# OSSI-1_LED_Controller.net
KiCad netlist of a schematic drawn in EAGLE
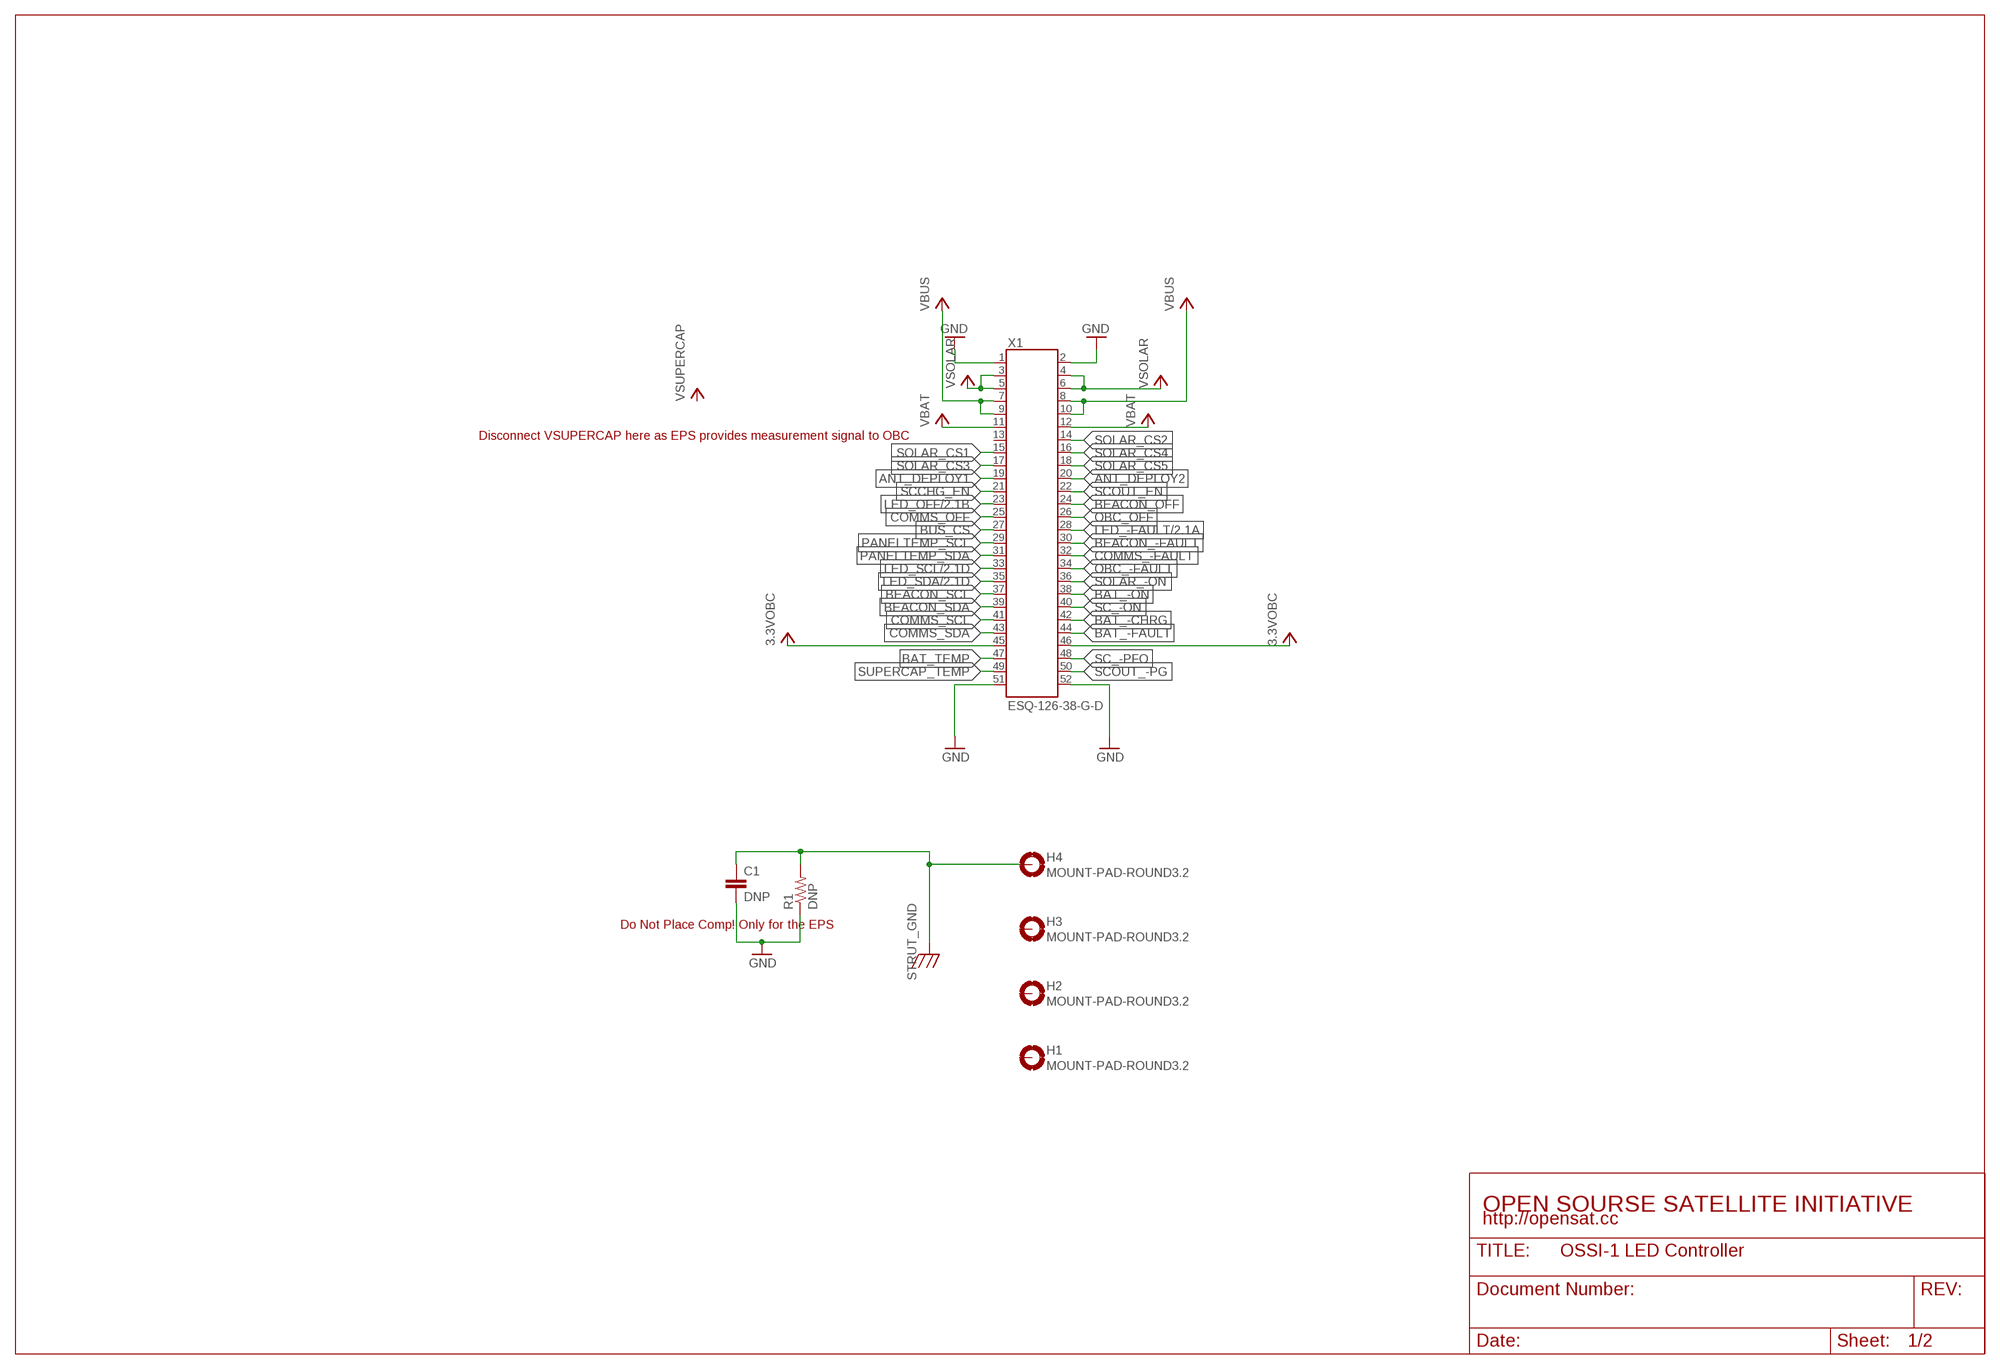
[diagram p0: schematic, sheet 1]
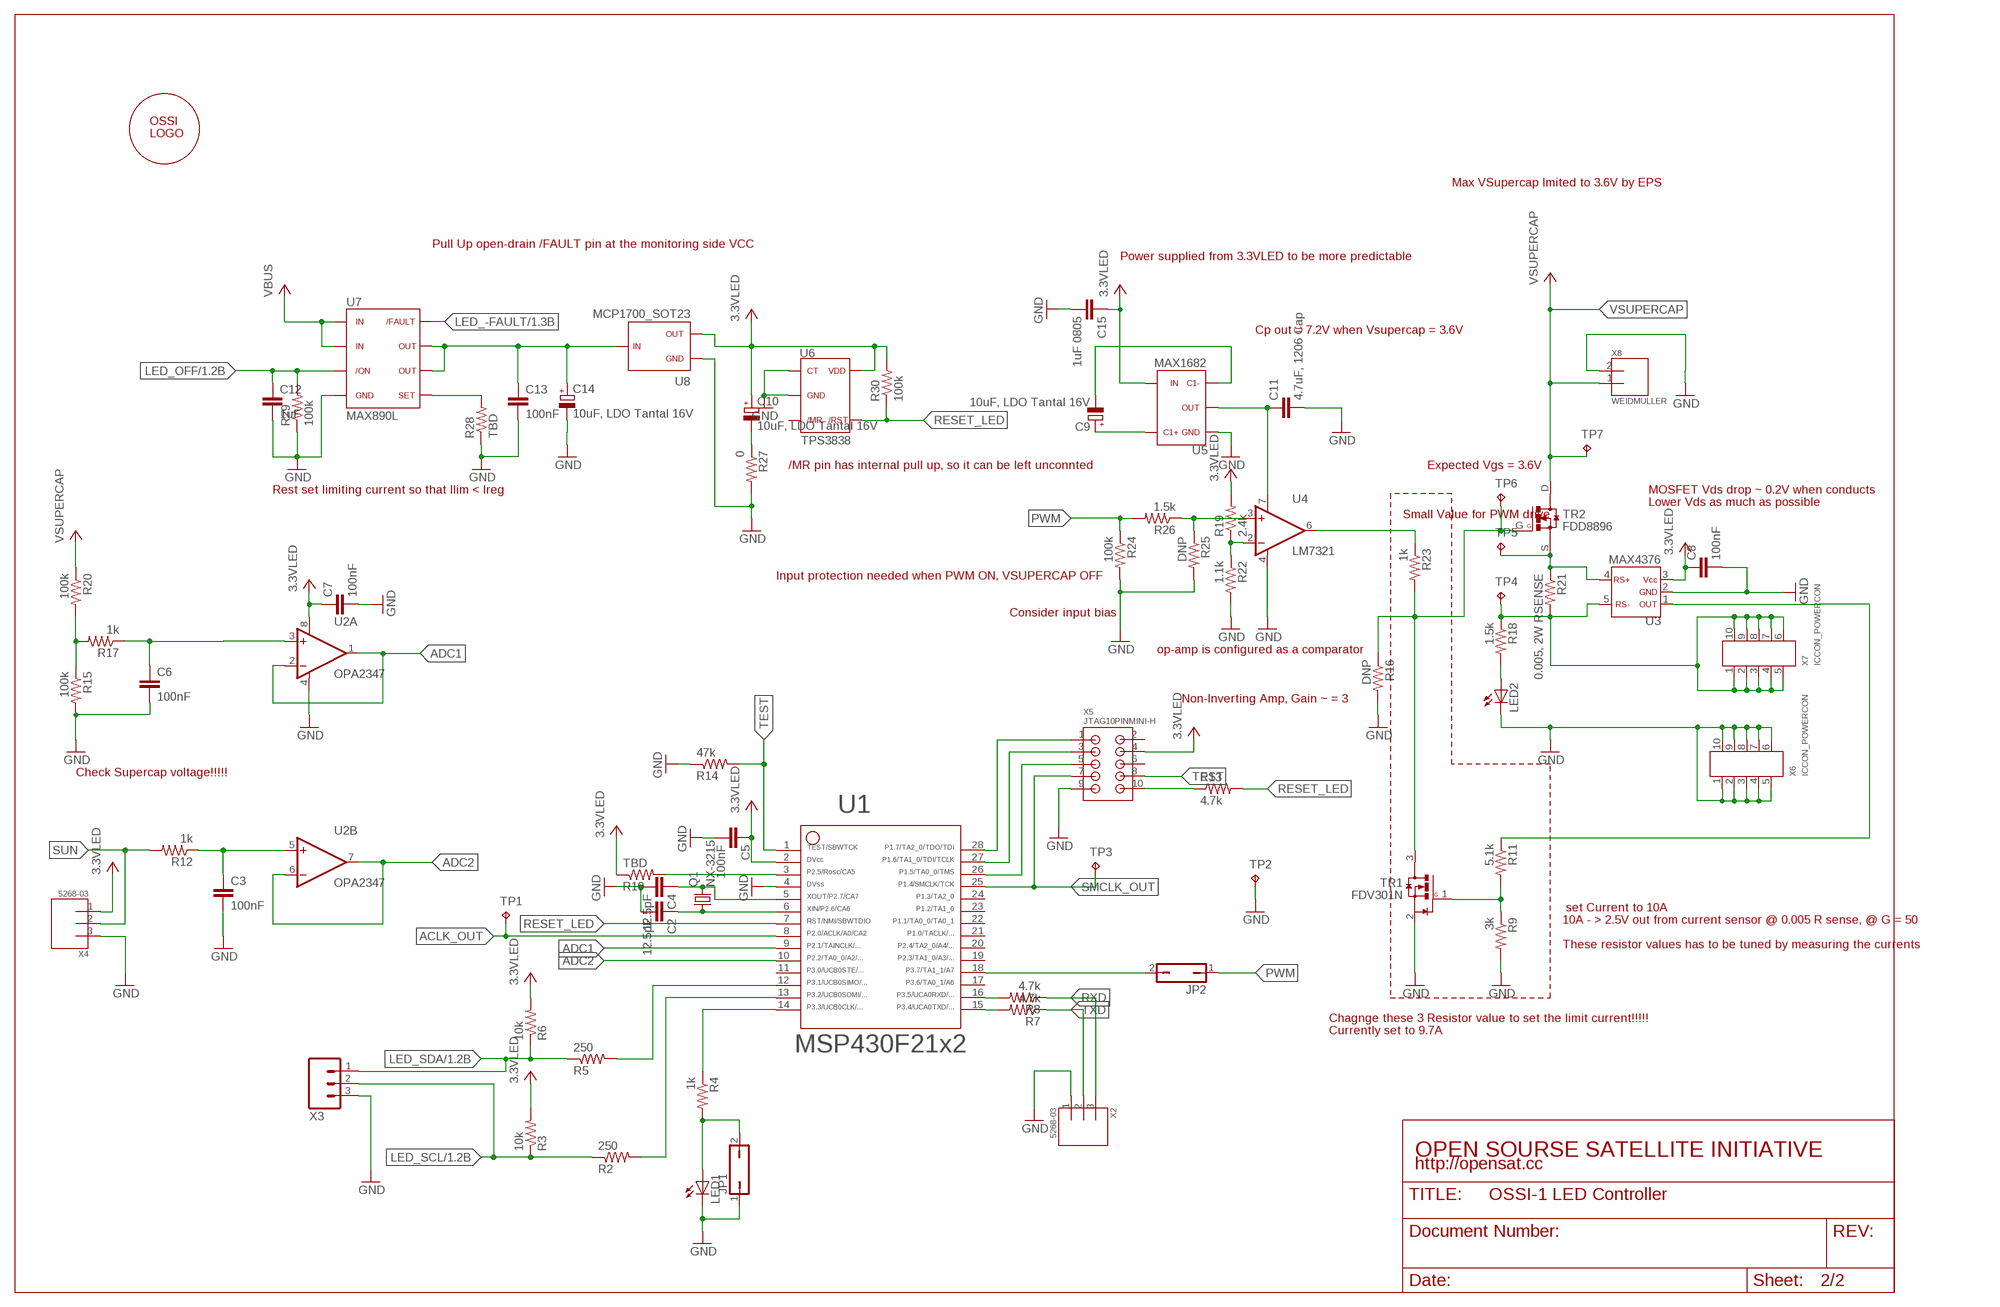
[diagram p1: schematic, sheet 2]

(export (version "E")
  (design (tool "Eeschema 10.0.6"))
  (components
    (comp (ref "C1")
      (value "DNP")
      (footprint "eagle-import:C0805(2012)")
      (libsource (lib "eagle-import") (part "C0805(2012)"))
    )
    (comp (ref "H1")
      (value "MOUNT-PAD-ROUND3.2")
      (footprint "eagle-import:3.2-PAD-ROUND")
      (libsource (lib "eagle-import") (part "MOUNT-PAD-ROUND3.2"))
    )
    (comp (ref "H2")
      (value "MOUNT-PAD-ROUND3.2")
      (footprint "eagle-import:3.2-PAD-ROUND")
      (libsource (lib "eagle-import") (part "MOUNT-PAD-ROUND3.2"))
    )
    (comp (ref "H3")
      (value "MOUNT-PAD-ROUND3.2")
      (footprint "eagle-import:3.2-PAD-ROUND")
      (libsource (lib "eagle-import") (part "MOUNT-PAD-ROUND3.2"))
    )
    (comp (ref "H4")
      (value "MOUNT-PAD-ROUND3.2")
      (footprint "eagle-import:3.2-PAD-ROUND")
      (libsource (lib "eagle-import") (part "MOUNT-PAD-ROUND3.2"))
    )
    (comp (ref "R1")
      (value "DNP")
      (footprint "eagle-import:WSL1206")
      (libsource (lib "eagle-import") (part "RWSL1206"))
    )
    (comp (ref "X1")
      (value "ESQ-126-38-G-D")
      (footprint "eagle-import:ESQ-126-XX-X-D")
      (libsource (lib "eagle-import") (part "ESQ-126-38-G-D"))
    )
    (comp (ref "C2")
      (value "12.5pF")
      (footprint "eagle-import:C0603(1608)")
      (libsource (lib "eagle-import") (part "C0603(1608)"))
    )
    (comp (ref "C3")
      (value "100nF")
      (footprint "eagle-import:C0603(1608)")
      (libsource (lib "eagle-import") (part "C0603(1608)"))
    )
    (comp (ref "C4")
      (value "12.5pF")
      (footprint "eagle-import:C0603(1608)")
      (libsource (lib "eagle-import") (part "C0603(1608)"))
    )
    (comp (ref "C5")
      (value "100nF")
      (footprint "eagle-import:C0603(1608)")
      (libsource (lib "eagle-import") (part "C0603(1608)"))
    )
    (comp (ref "C6")
      (value "100nF")
      (footprint "eagle-import:C0603(1608)")
      (libsource (lib "eagle-import") (part "C0603(1608)"))
    )
    (comp (ref "C7")
      (value "100nF")
      (footprint "eagle-import:C0603(1608)")
      (libsource (lib "eagle-import") (part "C0603(1608)"))
    )
    (comp (ref "C8")
      (value "100nF")
      (footprint "eagle-import:C0603(1608)")
      (libsource (lib "eagle-import") (part "C0603(1608)"))
    )
    (comp (ref "C9")
      (value "10uF, LDO Tantal 16V")
      (footprint "eagle-import:C1206(3216)-A")
      (libsource (lib "eagle-import") (part "C-TANTAL-A"))
    )
    (comp (ref "C10")
      (value "10uF, LDO Tantal 16V")
      (footprint "eagle-import:C1206(3216)-A")
      (libsource (lib "eagle-import") (part "C-TANTAL-A"))
    )
    (comp (ref "C11")
      (value "4.7uF, 1206 Cap")
      (footprint "eagle-import:C1206-GCM31")
      (libsource (lib "eagle-import") (part "C1206(3216)-GCM31"))
    )
    (comp (ref "C12")
      (value "1uF")
      (footprint "eagle-import:C0603(1608)")
      (libsource (lib "eagle-import") (part "C0603(1608)"))
    )
    (comp (ref "C13")
      (value "100nF")
      (footprint "eagle-import:C0603(1608)")
      (libsource (lib "eagle-import") (part "C0603(1608)"))
    )
    (comp (ref "C14")
      (value "10uF, LDO Tantal 16V")
      (footprint "eagle-import:C1206(3216)-A")
      (libsource (lib "eagle-import") (part "C-TANTAL-A"))
    )
    (comp (ref "C15")
      (value "1uF 0805")
      (footprint "eagle-import:C0805(2012)")
      (libsource (lib "eagle-import") (part "C0805(2012)"))
    )
    (comp (ref "JP1")
      (value "JP1Q")
      (footprint "eagle-import:JP1")
      (libsource (lib "eagle-import") (part "JP1Q"))
    )
    (comp (ref "JP2")
      (value "JP1Q")
      (footprint "eagle-import:JP1")
      (libsource (lib "eagle-import") (part "JP1Q"))
    )
    (comp (ref "LED1")
      (value "LED0603")
      (footprint "eagle-import:LED-0603")
      (libsource (lib "eagle-import") (part "LED0603"))
    )
    (comp (ref "LED2")
      (value "LEDCHIPLED_0603")
      (footprint "eagle-import:CHIPLED_0603")
      (libsource (lib "eagle-import") (part "LEDCHIPLED_0603"))
    )
    (comp (ref "Q1")
      (value "NX-3215")
      (footprint "eagle-import:NX-3215")
      (libsource (lib "eagle-import") (part "NX-3215"))
    )
    (comp (ref "R2")
      (value "250")
      (footprint "eagle-import:R0603(1608)")
      (libsource (lib "eagle-import") (part "R0603(1608)"))
    )
    (comp (ref "R3")
      (value "10k")
      (footprint "eagle-import:R0603(1608)")
      (libsource (lib "eagle-import") (part "R0603(1608)"))
    )
    (comp (ref "R4")
      (value "1k")
      (footprint "eagle-import:R0603(1608)")
      (libsource (lib "eagle-import") (part "R0603(1608)"))
    )
    (comp (ref "R5")
      (value "250")
      (footprint "eagle-import:R0603(1608)")
      (libsource (lib "eagle-import") (part "R0603(1608)"))
    )
    (comp (ref "R6")
      (value "10k")
      (footprint "eagle-import:R0603(1608)")
      (libsource (lib "eagle-import") (part "R0603(1608)"))
    )
    (comp (ref "R7")
      (value "4.7k")
      (footprint "eagle-import:R0603(1608)")
      (libsource (lib "eagle-import") (part "R0603(1608)"))
    )
    (comp (ref "R8")
      (value "4.7k")
      (footprint "eagle-import:R0603(1608)")
      (libsource (lib "eagle-import") (part "R0603(1608)"))
    )
    (comp (ref "R9")
      (value "3k")
      (footprint "eagle-import:R0603(1608)")
      (libsource (lib "eagle-import") (part "R0603(1608)"))
    )
    (comp (ref "R10")
      (value "TBD")
      (footprint "eagle-import:R0603(1608)")
      (libsource (lib "eagle-import") (part "R0603(1608)"))
    )
    (comp (ref "R11")
      (value "5.1k")
      (footprint "eagle-import:R0603(1608)")
      (libsource (lib "eagle-import") (part "R0603(1608)"))
    )
    (comp (ref "R12")
      (value "1k")
      (footprint "eagle-import:R0603(1608)")
      (libsource (lib "eagle-import") (part "R0603(1608)"))
    )
    (comp (ref "R13")
      (value "4.7k")
      (footprint "eagle-import:R0603(1608)")
      (libsource (lib "eagle-import") (part "R0603(1608)"))
    )
    (comp (ref "R14")
      (value "47k")
      (footprint "eagle-import:R0603(1608)")
      (libsource (lib "eagle-import") (part "R0603(1608)"))
    )
    (comp (ref "R15")
      (value "100k")
      (footprint "eagle-import:R0603(1608)")
      (libsource (lib "eagle-import") (part "R0603(1608)"))
    )
    (comp (ref "R16")
      (value "DNP")
      (footprint "eagle-import:R0603(1608)")
      (libsource (lib "eagle-import") (part "R0603(1608)"))
    )
    (comp (ref "R17")
      (value "1k")
      (footprint "eagle-import:R0603(1608)")
      (libsource (lib "eagle-import") (part "R0603(1608)"))
    )
    (comp (ref "R18")
      (value "1.5k")
      (footprint "eagle-import:R0603(1608)")
      (libsource (lib "eagle-import") (part "R0603(1608)"))
    )
    (comp (ref "R19")
      (value "2.4k")
      (footprint "eagle-import:R0603(1608)")
      (libsource (lib "eagle-import") (part "R0603(1608)"))
    )
    (comp (ref "R20")
      (value "100k")
      (footprint "eagle-import:R0603(1608)")
      (libsource (lib "eagle-import") (part "R0603(1608)"))
    )
    (comp (ref "R21")
      (value "0.005, 2W RSENSE")
      (footprint "eagle-import:R4527(12070)")
      (libsource (lib "eagle-import") (part "RWSR2"))
    )
    (comp (ref "R22")
      (value "1.1k")
      (footprint "eagle-import:R0603(1608)")
      (libsource (lib "eagle-import") (part "R0603(1608)"))
    )
    (comp (ref "R23")
      (value "1k")
      (footprint "eagle-import:R0603(1608)")
      (libsource (lib "eagle-import") (part "R0603(1608)"))
    )
    (comp (ref "R24")
      (value "100k")
      (footprint "eagle-import:R0603(1608)")
      (libsource (lib "eagle-import") (part "R0603(1608)"))
    )
    (comp (ref "R25")
      (value "DNP")
      (footprint "eagle-import:R0603(1608)")
      (libsource (lib "eagle-import") (part "R0603(1608)"))
    )
    (comp (ref "R26")
      (value "1.5k")
      (footprint "eagle-import:R0603(1608)")
      (libsource (lib "eagle-import") (part "R0603(1608)"))
    )
    (comp (ref "R27")
      (value "0")
      (footprint "eagle-import:R0603(1608)")
      (libsource (lib "eagle-import") (part "R0603(1608)"))
    )
    (comp (ref "R28")
      (value "TBD")
      (footprint "eagle-import:R0603(1608)")
      (libsource (lib "eagle-import") (part "R0603(1608)"))
    )
    (comp (ref "R29")
      (value "100k")
      (footprint "eagle-import:R0603(1608)")
      (libsource (lib "eagle-import") (part "R0603(1608)"))
    )
    (comp (ref "R30")
      (value "100k")
      (footprint "eagle-import:R0603(1608)")
      (libsource (lib "eagle-import") (part "R0603(1608)"))
    )
    (comp (ref "TP1")
      (value "TP")
      (footprint "eagle-import:TP-13")
      (libsource (lib "eagle-import") (part "TP"))
    )
    (comp (ref "TP2")
      (value "TP")
      (footprint "eagle-import:TP-13")
      (libsource (lib "eagle-import") (part "TP"))
    )
    (comp (ref "TP3")
      (value "TP")
      (footprint "eagle-import:TP-13")
      (libsource (lib "eagle-import") (part "TP"))
    )
    (comp (ref "TP4")
      (value "TP")
      (footprint "eagle-import:TP-13")
      (libsource (lib "eagle-import") (part "TP"))
    )
    (comp (ref "TP5")
      (value "TP")
      (footprint "eagle-import:TP-13")
      (libsource (lib "eagle-import") (part "TP"))
    )
    (comp (ref "TP6")
      (value "TP")
      (footprint "eagle-import:TP-13")
      (libsource (lib "eagle-import") (part "TP"))
    )
    (comp (ref "TP7")
      (value "TP")
      (footprint "eagle-import:TP-13")
      (libsource (lib "eagle-import") (part "TP"))
    )
    (comp (ref "TR1")
      (value "FDV301N")
      (footprint "eagle-import:SOT23")
      (libsource (lib "eagle-import") (part "FDV301N"))
    )
    (comp (ref "TR2")
      (value "FDD8896")
      (footprint "eagle-import:TO252")
      (libsource (lib "eagle-import") (part "FDD8896"))
    )
    (comp (ref "U$")
      (value "OSSILOGORECT")
      (footprint "eagle-import:OSSILOGORECT1005")
      (libsource (lib "eagle-import") (part "OSSILOGORECT"))
    )
    (comp (ref "U1")
      (value "MSP430F2132")
      (footprint "eagle-import:PW28")
      (libsource (lib "eagle-import") (part "MSP430F2132"))
    )
    (comp (ref "U2")
      (value "OPA2347")
      (footprint "eagle-import:SOT23-8DCN")
      (libsource (lib "eagle-import") (part "OPA2347"))
    )
    (comp (ref "U3")
      (value "MAX4376")
      (footprint "eagle-import:SOT23-5DBV")
      (libsource (lib "eagle-import") (part "MAX4376"))
    )
    (comp (ref "U4")
      (value "LM7321")
      (footprint "eagle-import:SO8")
      (libsource (lib "eagle-import") (part "LM7321"))
    )
    (comp (ref "U5")
      (value "MAX1682")
      (footprint "eagle-import:SOT23-5DBV")
      (libsource (lib "eagle-import") (part "MAX1682"))
    )
    (comp (ref "U6")
      (value "TPS3838")
      (footprint "eagle-import:SOT23-5DBV")
      (libsource (lib "eagle-import") (part "TPS3838"))
    )
    (comp (ref "U7")
      (value "MAX890L")
      (footprint "eagle-import:SO8")
      (libsource (lib "eagle-import") (part "MAX890L"))
    )
    (comp (ref "U8")
      (value "MCP1700_SOT23")
      (footprint "eagle-import:SOT23")
      (libsource (lib "eagle-import") (part "MCP1700_SOT23"))
    )
    (comp (ref "X2")
      (value "5268-03")
      (footprint "eagle-import:5268-03")
      (libsource (lib "eagle-import") (part "5268-03"))
    )
    (comp (ref "X3")
      (value "M03PTH")
      (footprint "eagle-import:1X03")
      (libsource (lib "eagle-import") (part "M03PTH"))
    )
    (comp (ref "X4")
      (value "5268-03")
      (footprint "eagle-import:5268-03")
      (libsource (lib "eagle-import") (part "5268-03"))
    )
    (comp (ref "X5")
      (value "JTAG10PINMINI-H")
      (footprint "eagle-import:M50-3200545")
      (libsource (lib "eagle-import") (part "JTAG10PINMINI-H"))
    )
    (comp (ref "X6")
      (value "ICCON_POWERCON")
      (footprint "eagle-import:ICCON6643220-1")
      (libsource (lib "eagle-import") (part "ICCON_POWERCON"))
    )
    (comp (ref "X7")
      (value "ICCON_POWERCON")
      (footprint "eagle-import:ICCON6643220-1")
      (libsource (lib "eagle-import") (part "ICCON_POWERCON"))
    )
    (comp (ref "X8")
      (value "WEIDMULLER")
      (footprint "eagle-import:WEIDMULLER1760490000")
      (libsource (lib "eagle-import") (part "WEIDMULLER"))
    )
  )
  (nets
    (net (code "1") (name "3.3VLED") (class "Default")
      (node (ref "C10") (pin "1") (pinfunction "+_1") (pintype "passive"))
      (node (ref "C15") (pin "1") (pinfunction "1_1") (pintype "passive"))
      (node (ref "C5") (pin "1") (pinfunction "1_1") (pintype "passive"))
      (node (ref "C7") (pin "1") (pinfunction "1_1") (pintype "passive"))
      (node (ref "C8") (pin "1") (pinfunction "1_1") (pintype "passive"))
      (node (ref "R10") (pin "1") (pinfunction "1_1") (pintype "passive"))
      (node (ref "R19") (pin "2") (pinfunction "2_2") (pintype "passive"))
      (node (ref "R3") (pin "2") (pinfunction "2_2") (pintype "passive"))
      (node (ref "R30") (pin "2") (pinfunction "2_2") (pintype "passive"))
      (node (ref "R6") (pin "2") (pinfunction "2_2") (pintype "passive"))
      (node (ref "U1") (pin "2") (pinfunction "2_2") (pintype "power_in"))
      (node (ref "U2") (pin "8") (pinfunction "V+_8") (pintype "power_in"))
      (node (ref "U3") (pin "3") (pinfunction "P$3_3") (pintype "power_in"))
      (node (ref "U5") (pin "4") (pinfunction "P$4_4") (pintype "power_in"))
      (node (ref "U6") (pin "5") (pinfunction "P$5_5") (pintype "power_in"))
      (node (ref "U8") (pin "2") (pinfunction "2_2") (pintype "power_in"))
      (node (ref "X4") (pin "1") (pinfunction "1_1") (pintype "bidirectional"))
      (node (ref "X5") (pin "4") (pinfunction "4_4") (pintype "bidirectional"))
    )
    (net (code "2") (name "3.3VOBC") (class "Default")
      (node (ref "X1") (pin "45") (pinfunction "45_45") (pintype "bidirectional"))
      (node (ref "X1") (pin "46") (pinfunction "46_46") (pintype "bidirectional"))
    )
    (net (code "3") (name "ACLK_OUT") (class "Default")
      (node (ref "TP1") (pin "TP") (pinfunction "TP_TP") (pintype "input"))
      (node (ref "U1") (pin "8") (pinfunction "8_8") (pintype "bidirectional"))
    )
    (net (code "4") (name "ADC1") (class "Default")
      (node (ref "U1") (pin "9") (pinfunction "9_9") (pintype "bidirectional"))
      (node (ref "U2") (pin "1") (pinfunction "OUT_1") (pintype "output"))
      (node (ref "U2") (pin "2") (pinfunction "-IN_2") (pintype "input"))
    )
    (net (code "5") (name "ADC2") (class "Default")
      (node (ref "U1") (pin "10") (pinfunction "10_10") (pintype "bidirectional"))
      (node (ref "U2") (pin "6") (pinfunction "-IN_6") (pintype "input"))
      (node (ref "U2") (pin "7") (pinfunction "OUT_7") (pintype "output"))
    )
    (net (code "6") (name "ANT_DEPLOY1") (class "Default")
      (node (ref "X1") (pin "19") (pinfunction "19_19") (pintype "bidirectional"))
    )
    (net (code "7") (name "ANT_DEPLOY2") (class "Default")
      (node (ref "X1") (pin "20") (pinfunction "20_20") (pintype "bidirectional"))
    )
    (net (code "8") (name "BAT_-CHRG") (class "Default")
      (node (ref "X1") (pin "42") (pinfunction "42_42") (pintype "bidirectional"))
    )
    (net (code "9") (name "BAT_-FAULT") (class "Default")
      (node (ref "X1") (pin "44") (pinfunction "44_44") (pintype "bidirectional"))
    )
    (net (code "10") (name "BAT_-ON") (class "Default")
      (node (ref "X1") (pin "38") (pinfunction "38_38") (pintype "bidirectional"))
    )
    (net (code "11") (name "BAT_TEMP") (class "Default")
      (node (ref "X1") (pin "47") (pinfunction "47_47") (pintype "bidirectional"))
    )
    (net (code "12") (name "BEACON_-FAULT") (class "Default")
      (node (ref "X1") (pin "30") (pinfunction "30_30") (pintype "bidirectional"))
    )
    (net (code "13") (name "BEACON_OFF") (class "Default")
      (node (ref "X1") (pin "24") (pinfunction "24_24") (pintype "bidirectional"))
    )
    (net (code "14") (name "BEACON_SCL") (class "Default")
      (node (ref "X1") (pin "37") (pinfunction "37_37") (pintype "bidirectional"))
    )
    (net (code "15") (name "BEACON_SDA") (class "Default")
      (node (ref "X1") (pin "39") (pinfunction "39_39") (pintype "bidirectional"))
    )
    (net (code "16") (name "BUS_CS") (class "Default")
      (node (ref "X1") (pin "27") (pinfunction "27_27") (pintype "bidirectional"))
    )
    (net (code "17") (name "COMMS_-FAULT") (class "Default")
      (node (ref "X1") (pin "32") (pinfunction "32_32") (pintype "bidirectional"))
    )
    (net (code "18") (name "COMMS_OFF") (class "Default")
      (node (ref "X1") (pin "25") (pinfunction "25_25") (pintype "bidirectional"))
    )
    (net (code "19") (name "COMMS_SCL") (class "Default")
      (node (ref "X1") (pin "41") (pinfunction "41_41") (pintype "bidirectional"))
    )
    (net (code "20") (name "COMMS_SDA") (class "Default")
      (node (ref "X1") (pin "43") (pinfunction "43_43") (pintype "bidirectional"))
    )
    (net (code "21") (name "GND") (class "Default")
      (node (ref "C1") (pin "2") (pinfunction "2_2") (pintype "passive"))
      (node (ref "C11") (pin "P$2") (pinfunction "2_P$2") (pintype "passive"))
      (node (ref "C12") (pin "2") (pinfunction "2_2") (pintype "passive"))
      (node (ref "C13") (pin "2") (pinfunction "2_2") (pintype "passive"))
      (node (ref "C14") (pin "2") (pinfunction "-_2") (pintype "passive"))
      (node (ref "C15") (pin "2") (pinfunction "2_2") (pintype "passive"))
      (node (ref "C2") (pin "2") (pinfunction "2_2") (pintype "passive"))
      (node (ref "C3") (pin "2") (pinfunction "2_2") (pintype "passive"))
      (node (ref "C4") (pin "2") (pinfunction "2_2") (pintype "passive"))
      (node (ref "C5") (pin "2") (pinfunction "2_2") (pintype "passive"))
      (node (ref "C6") (pin "2") (pinfunction "2_2") (pintype "passive"))
      (node (ref "C7") (pin "2") (pinfunction "2_2") (pintype "passive"))
      (node (ref "C8") (pin "2") (pinfunction "2_2") (pintype "passive"))
      (node (ref "JP1") (pin "1") (pinfunction "1_1") (pintype "passive"))
      (node (ref "LED1") (pin "C") (pinfunction "C_C") (pintype "passive"))
      (node (ref "LED2") (pin "C") (pinfunction "C_C") (pintype "passive"))
      (node (ref "R1") (pin "P$1") (pinfunction "1_P$1") (pintype "passive"))
      (node (ref "R14") (pin "1") (pinfunction "1_1") (pintype "passive"))
      (node (ref "R15") (pin "2") (pinfunction "2_2") (pintype "passive"))
      (node (ref "R16") (pin "2") (pinfunction "2_2") (pintype "passive"))
      (node (ref "R22") (pin "2") (pinfunction "2_2") (pintype "passive"))
      (node (ref "R24") (pin "2") (pinfunction "2_2") (pintype "passive"))
      (node (ref "R25") (pin "2") (pinfunction "2_2") (pintype "passive"))
      (node (ref "R27") (pin "2") (pinfunction "2_2") (pintype "passive"))
      (node (ref "R28") (pin "1") (pinfunction "1_1") (pintype "passive"))
      (node (ref "R29") (pin "1") (pinfunction "1_1") (pintype "passive"))
      (node (ref "R9") (pin "2") (pinfunction "2_2") (pintype "passive"))
      (node (ref "TP2") (pin "TP") (pinfunction "TP_TP") (pintype "input"))
      (node (ref "TR1") (pin "2") (pinfunction "S_2") (pintype "bidirectional"))
      (node (ref "U1") (pin "4") (pinfunction "4_4") (pintype "power_in"))
      (node (ref "U2") (pin "4") (pinfunction "V-_4") (pintype "power_in"))
      (node (ref "U3") (pin "2") (pinfunction "P$2_2") (pintype "power_in"))
      (node (ref "U4") (pin "4") (pinfunction "V-_4") (pintype "power_in"))
      (node (ref "U5") (pin "1") (pinfunction "P$1_1") (pintype "power_in"))
      (node (ref "U6") (pin "1") (pinfunction "P$1_1") (pintype "bidirectional"))
      (node (ref "U6") (pin "2") (pinfunction "P$2_2") (pintype "power_in"))
      (node (ref "U7") (pin "4") (pinfunction "P$4_4") (pintype "power_in"))
      (node (ref "U8") (pin "1") (pinfunction "1_1") (pintype "power_in"))
      (node (ref "X1") (pin "1") (pinfunction "1_1") (pintype "bidirectional"))
      (node (ref "X1") (pin "2") (pinfunction "2_2") (pintype "bidirectional"))
      (node (ref "X1") (pin "51") (pinfunction "51_51") (pintype "bidirectional"))
      (node (ref "X1") (pin "52") (pinfunction "52_52") (pintype "bidirectional"))
      (node (ref "X2") (pin "1") (pinfunction "1_1") (pintype "bidirectional"))
      (node (ref "X3") (pin "3") (pinfunction "3_3") (pintype "passive"))
      (node (ref "X4") (pin "3") (pinfunction "3_3") (pintype "bidirectional"))
      (node (ref "X5") (pin "9") (pinfunction "9_9") (pintype "bidirectional"))
      (node (ref "X6") (pin "1") (pinfunction "P$1_1") (pintype "bidirectional"))
      (node (ref "X6") (pin "10") (pinfunction "P$10_10") (pintype "bidirectional"))
      (node (ref "X6") (pin "2") (pinfunction "P$2_2") (pintype "bidirectional"))
      (node (ref "X6") (pin "3") (pinfunction "P$3_3") (pintype "bidirectional"))
      (node (ref "X6") (pin "4") (pinfunction "P$4_4") (pintype "bidirectional"))
      (node (ref "X6") (pin "5") (pinfunction "P$5_5") (pintype "bidirectional"))
      (node (ref "X6") (pin "6") (pinfunction "P$6_6") (pintype "bidirectional"))
      (node (ref "X6") (pin "7") (pinfunction "P$7_7") (pintype "bidirectional"))
      (node (ref "X6") (pin "8") (pinfunction "P$8_8") (pintype "bidirectional"))
      (node (ref "X6") (pin "9") (pinfunction "P$9_9") (pintype "bidirectional"))
      (node (ref "X8") (pin "2") (pinfunction "2_2") (pintype "bidirectional"))
    )
    (net (code "22") (name "LED_-FAULT") (class "Default")
      (node (ref "U7") (pin "8") (pinfunction "P$8_8") (pintype "output"))
      (node (ref "X1") (pin "28") (pinfunction "28_28") (pintype "bidirectional"))
    )
    (net (code "23") (name "LED_OFF") (class "Default")
      (node (ref "C12") (pin "1") (pinfunction "1_1") (pintype "passive"))
      (node (ref "R29") (pin "2") (pinfunction "2_2") (pintype "passive"))
      (node (ref "U7") (pin "3") (pinfunction "P$3_3") (pintype "input"))
      (node (ref "X1") (pin "23") (pinfunction "23_23") (pintype "bidirectional"))
    )
    (net (code "24") (name "LED_SCL") (class "Default")
      (node (ref "R2") (pin "1") (pinfunction "1_1") (pintype "passive"))
      (node (ref "R3") (pin "1") (pinfunction "1_1") (pintype "passive"))
      (node (ref "X1") (pin "33") (pinfunction "33_33") (pintype "bidirectional"))
      (node (ref "X3") (pin "2") (pinfunction "2_2") (pintype "passive"))
    )
    (net (code "25") (name "LED_SDA") (class "Default")
      (node (ref "R5") (pin "1") (pinfunction "1_1") (pintype "passive"))
      (node (ref "R6") (pin "1") (pinfunction "1_1") (pintype "passive"))
      (node (ref "X1") (pin "35") (pinfunction "35_35") (pintype "bidirectional"))
      (node (ref "X3") (pin "1") (pinfunction "1_1") (pintype "passive"))
    )
    (net (code "26") (name "Net-(C2-Pad1)") (class "Default")
      (node (ref "C2") (pin "1") (pinfunction "1_1") (pintype "passive"))
      (node (ref "Q1") (pin "1") (pinfunction "1_1") (pintype "passive"))
      (node (ref "U1") (pin "6") (pinfunction "6_6") (pintype "bidirectional"))
    )
    (net (code "27") (name "Net-(C4-Pad1)") (class "Default")
      (node (ref "C4") (pin "1") (pinfunction "1_1") (pintype "passive"))
      (node (ref "Q1") (pin "2") (pinfunction "2_2") (pintype "passive"))
      (node (ref "U1") (pin "5") (pinfunction "5_5") (pintype "bidirectional"))
    )
    (net (code "28") (name "Net-(C9-+)") (class "Default")
      (node (ref "C9") (pin "1") (pinfunction "+_1") (pintype "passive"))
      (node (ref "U5") (pin "5") (pinfunction "P$5_5") (pintype "passive"))
    )
    (net (code "29") (name "Net-(C9--)") (class "Default")
      (node (ref "C9") (pin "2") (pinfunction "-_2") (pintype "passive"))
      (node (ref "U5") (pin "3") (pinfunction "P$3_3") (pintype "passive"))
    )
    (net (code "30") (name "Net-(C10--)") (class "Default")
      (node (ref "C10") (pin "2") (pinfunction "-_2") (pintype "passive"))
      (node (ref "R27") (pin "1") (pinfunction "1_1") (pintype "passive"))
    )
    (net (code "31") (name "Net-(C11-1)") (class "Default")
      (node (ref "C11") (pin "P$1") (pinfunction "1_P$1") (pintype "passive"))
      (node (ref "U4") (pin "7") (pinfunction "V+_7") (pintype "power_in"))
      (node (ref "U5") (pin "2") (pinfunction "P$2_2") (pintype "power_in"))
    )
    (net (code "32") (name "Net-(C14-+)") (class "Default")
      (node (ref "C13") (pin "1") (pinfunction "1_1") (pintype "passive"))
      (node (ref "C14") (pin "1") (pinfunction "+_1") (pintype "passive"))
      (node (ref "U7") (pin "6") (pinfunction "P$6_6") (pintype "output"))
      (node (ref "U7") (pin "7") (pinfunction "P$7_7") (pintype "output"))
      (node (ref "U8") (pin "3") (pinfunction "3_3") (pintype "power_in"))
    )
    (net (code "33") (name "Net-(JP1-Pad2)") (class "Default")
      (node (ref "JP1") (pin "2") (pinfunction "2_2") (pintype "passive"))
      (node (ref "LED1") (pin "A") (pinfunction "A_A") (pintype "passive"))
      (node (ref "R4") (pin "2") (pinfunction "2_2") (pintype "passive"))
    )
    (net (code "34") (name "Net-(JP2-Pad2)") (class "Default")
      (node (ref "JP2") (pin "2") (pinfunction "2_2") (pintype "passive"))
      (node (ref "U1") (pin "18") (pinfunction "18_18") (pintype "bidirectional"))
    )
    (net (code "35") (name "Net-(LED2-PadA)") (class "Default")
      (node (ref "LED2") (pin "A") (pinfunction "A_A") (pintype "passive"))
      (node (ref "R18") (pin "2") (pinfunction "2_2") (pintype "passive"))
    )
    (net (code "36") (name "Net-(R2-Pad2)") (class "Default")
      (node (ref "R2") (pin "2") (pinfunction "2_2") (pintype "passive"))
      (node (ref "U1") (pin "13") (pinfunction "13_13") (pintype "bidirectional"))
    )
    (net (code "37") (name "Net-(R4-Pad1)") (class "Default")
      (node (ref "R4") (pin "1") (pinfunction "1_1") (pintype "passive"))
      (node (ref "U1") (pin "14") (pinfunction "14_14") (pintype "bidirectional"))
    )
    (net (code "38") (name "Net-(R5-Pad2)") (class "Default")
      (node (ref "R5") (pin "2") (pinfunction "2_2") (pintype "passive"))
      (node (ref "U1") (pin "12") (pinfunction "12_12") (pintype "bidirectional"))
    )
    (net (code "39") (name "Net-(R7-Pad2)") (class "Default")
      (node (ref "R7") (pin "2") (pinfunction "2_2") (pintype "passive"))
      (node (ref "U1") (pin "15") (pinfunction "15_15") (pintype "bidirectional"))
    )
    (net (code "40") (name "Net-(R8-Pad2)") (class "Default")
      (node (ref "R8") (pin "2") (pinfunction "2_2") (pintype "passive"))
      (node (ref "U1") (pin "16") (pinfunction "16_16") (pintype "bidirectional"))
    )
    (net (code "41") (name "Net-(R10-Pad2)") (class "Default")
      (node (ref "R10") (pin "2") (pinfunction "2_2") (pintype "passive"))
      (node (ref "U1") (pin "3") (pinfunction "3_3") (pintype "bidirectional"))
    )
    (net (code "42") (name "Net-(R13-Pad1)") (class "Default")
      (node (ref "R13") (pin "1") (pinfunction "1_1") (pintype "passive"))
      (node (ref "X5") (pin "10") (pinfunction "10_10") (pintype "bidirectional"))
    )
    (net (code "43") (name "Net-(R15-Pad1)") (class "Default")
      (node (ref "R15") (pin "1") (pinfunction "1_1") (pintype "passive"))
      (node (ref "R17") (pin "2") (pinfunction "2_2") (pintype "passive"))
      (node (ref "R20") (pin "2") (pinfunction "2_2") (pintype "passive"))
    )
    (net (code "44") (name "Net-(R21-1)") (class "Default")
      (node (ref "R21") (pin "P$1") (pinfunction "1_P$1") (pintype "passive"))
      (node (ref "TP5") (pin "TP") (pinfunction "TP_TP") (pintype "input"))
      (node (ref "TR2") (pin "S") (pinfunction "S_S") (pintype "bidirectional"))
      (node (ref "U3") (pin "4") (pinfunction "P$4_4") (pintype "input"))
    )
    (net (code "45") (name "Net-(R21-2)") (class "Default")
      (node (ref "R18") (pin "1") (pinfunction "1_1") (pintype "passive"))
      (node (ref "R21") (pin "P$2") (pinfunction "2_P$2") (pintype "passive"))
      (node (ref "TP4") (pin "TP") (pinfunction "TP_TP") (pintype "input"))
      (node (ref "U3") (pin "5") (pinfunction "P$5_5") (pintype "input"))
      (node (ref "X7") (pin "1") (pinfunction "P$1_1") (pintype "bidirectional"))
      (node (ref "X7") (pin "10") (pinfunction "P$10_10") (pintype "bidirectional"))
      (node (ref "X7") (pin "2") (pinfunction "P$2_2") (pintype "bidirectional"))
      (node (ref "X7") (pin "3") (pinfunction "P$3_3") (pintype "bidirectional"))
      (node (ref "X7") (pin "4") (pinfunction "P$4_4") (pintype "bidirectional"))
      (node (ref "X7") (pin "5") (pinfunction "P$5_5") (pintype "bidirectional"))
      (node (ref "X7") (pin "6") (pinfunction "P$6_6") (pintype "bidirectional"))
      (node (ref "X7") (pin "7") (pinfunction "P$7_7") (pintype "bidirectional"))
      (node (ref "X7") (pin "8") (pinfunction "P$8_8") (pintype "bidirectional"))
      (node (ref "X7") (pin "9") (pinfunction "P$9_9") (pintype "bidirectional"))
    )
    (net (code "46") (name "Net-(TR1-D)") (class "Default")
      (node (ref "R16") (pin "1") (pinfunction "1_1") (pintype "passive"))
      (node (ref "R23") (pin "2") (pinfunction "2_2") (pintype "passive"))
      (node (ref "TP6") (pin "TP") (pinfunction "TP_TP") (pintype "input"))
      (node (ref "TR1") (pin "3") (pinfunction "D_3") (pintype "bidirectional"))
      (node (ref "TR2") (pin "G") (pinfunction "G_G") (pintype "bidirectional"))
    )
    (net (code "47") (name "Net-(TR1-G)") (class "Default")
      (node (ref "R11") (pin "2") (pinfunction "2_2") (pintype "passive"))
      (node (ref "R9") (pin "1") (pinfunction "1_1") (pintype "passive"))
      (node (ref "TR1") (pin "1") (pinfunction "G_1") (pintype "bidirectional"))
    )
    (net (code "48") (name "Net-(U1-Pad26)") (class "Default")
      (node (ref "U1") (pin "26") (pinfunction "26_26") (pintype "bidirectional"))
      (node (ref "X5") (pin "5") (pinfunction "5_5") (pintype "bidirectional"))
    )
    (net (code "49") (name "Net-(U1-Pad27)") (class "Default")
      (node (ref "U1") (pin "27") (pinfunction "27_27") (pintype "bidirectional"))
      (node (ref "X5") (pin "3") (pinfunction "3_3") (pintype "bidirectional"))
    )
    (net (code "50") (name "Net-(U1-Pad28)") (class "Default")
      (node (ref "U1") (pin "28") (pinfunction "28_28") (pintype "bidirectional"))
      (node (ref "X5") (pin "1") (pinfunction "1_1") (pintype "bidirectional"))
    )
    (net (code "51") (name "Net-(U2A-+IN)") (class "Default")
      (node (ref "C6") (pin "1") (pinfunction "1_1") (pintype "passive"))
      (node (ref "R17") (pin "1") (pinfunction "1_1") (pintype "passive"))
      (node (ref "U2") (pin "3") (pinfunction "+IN_3") (pintype "input"))
    )
    (net (code "52") (name "Net-(U2B-+IN)") (class "Default")
      (node (ref "C3") (pin "1") (pinfunction "1_1") (pintype "passive"))
      (node (ref "R12") (pin "1") (pinfunction "1_1") (pintype "passive"))
      (node (ref "U2") (pin "5") (pinfunction "+IN_5") (pintype "input"))
    )
    (net (code "53") (name "Net-(U3-P$1)") (class "Default")
      (node (ref "R11") (pin "1") (pinfunction "1_1") (pintype "passive"))
      (node (ref "U3") (pin "1") (pinfunction "P$1_1") (pintype "output"))
    )
    (net (code "54") (name "Net-(U4-+IN)") (class "Default")
      (node (ref "R25") (pin "1") (pinfunction "1_1") (pintype "passive"))
      (node (ref "R26") (pin "1") (pinfunction "1_1") (pintype "passive"))
      (node (ref "U4") (pin "3") (pinfunction "+IN_3") (pintype "input"))
    )
    (net (code "55") (name "Net-(U4--IN)") (class "Default")
      (node (ref "R19") (pin "1") (pinfunction "1_1") (pintype "passive"))
      (node (ref "R22") (pin "1") (pinfunction "1_1") (pintype "passive"))
      (node (ref "U4") (pin "2") (pinfunction "-IN_2") (pintype "input"))
    )
    (net (code "56") (name "Net-(U4-OUT)") (class "Default")
      (node (ref "R23") (pin "1") (pinfunction "1_1") (pintype "passive"))
      (node (ref "U4") (pin "6") (pinfunction "OUT_6") (pintype "output"))
    )
    (net (code "57") (name "Net-(U7-P$5)") (class "Default")
      (node (ref "R28") (pin "2") (pinfunction "2_2") (pintype "passive"))
      (node (ref "U7") (pin "5") (pinfunction "P$5_5") (pintype "passive"))
    )
    (net (code "58") (name "OBC_-FAULT") (class "Default")
      (node (ref "X1") (pin "34") (pinfunction "34_34") (pintype "bidirectional"))
    )
    (net (code "59") (name "OBC_OFF") (class "Default")
      (node (ref "X1") (pin "26") (pinfunction "26_26") (pintype "bidirectional"))
    )
    (net (code "60") (name "PANELTEMP_SCL") (class "Default")
      (node (ref "X1") (pin "29") (pinfunction "29_29") (pintype "bidirectional"))
    )
    (net (code "61") (name "PANELTEMP_SDA") (class "Default")
      (node (ref "X1") (pin "31") (pinfunction "31_31") (pintype "bidirectional"))
    )
    (net (code "62") (name "PWM") (class "Default")
      (node (ref "JP2") (pin "1") (pinfunction "1_1") (pintype "passive"))
      (node (ref "R24") (pin "1") (pinfunction "1_1") (pintype "passive"))
      (node (ref "R26") (pin "2") (pinfunction "2_2") (pintype "passive"))
    )
    (net (code "63") (name "RESET_LED") (class "Default")
      (node (ref "R13") (pin "2") (pinfunction "2_2") (pintype "passive"))
      (node (ref "R30") (pin "1") (pinfunction "1_1") (pintype "passive"))
      (node (ref "U1") (pin "7") (pinfunction "7_7") (pintype "input"))
      (node (ref "U6") (pin "4") (pinfunction "P$4_4") (pintype "output"))
    )
    (net (code "64") (name "RXD") (class "Default")
      (node (ref "R8") (pin "1") (pinfunction "1_1") (pintype "passive"))
      (node (ref "X2") (pin "3") (pinfunction "3_3") (pintype "bidirectional"))
    )
    (net (code "65") (name "SCCHG_EN") (class "Default")
      (node (ref "X1") (pin "21") (pinfunction "21_21") (pintype "bidirectional"))
    )
    (net (code "66") (name "SCOUT_-PG") (class "Default")
      (node (ref "X1") (pin "50") (pinfunction "50_50") (pintype "bidirectional"))
    )
    (net (code "67") (name "SCOUT_EN") (class "Default")
      (node (ref "X1") (pin "22") (pinfunction "22_22") (pintype "bidirectional"))
    )
    (net (code "68") (name "SC_-ON") (class "Default")
      (node (ref "X1") (pin "40") (pinfunction "40_40") (pintype "bidirectional"))
    )
    (net (code "69") (name "SC_-PFO") (class "Default")
      (node (ref "X1") (pin "48") (pinfunction "48_48") (pintype "bidirectional"))
    )
    (net (code "70") (name "SMCLK_OUT") (class "Default")
      (node (ref "TP3") (pin "TP") (pinfunction "TP_TP") (pintype "input"))
      (node (ref "U1") (pin "25") (pinfunction "25_25") (pintype "bidirectional"))
      (node (ref "X5") (pin "7") (pinfunction "7_7") (pintype "bidirectional"))
    )
    (net (code "71") (name "SOLAR_-ON") (class "Default")
      (node (ref "X1") (pin "36") (pinfunction "36_36") (pintype "bidirectional"))
    )
    (net (code "72") (name "SOLAR_CS1") (class "Default")
      (node (ref "X1") (pin "15") (pinfunction "15_15") (pintype "bidirectional"))
    )
    (net (code "73") (name "SOLAR_CS2") (class "Default")
      (node (ref "X1") (pin "14") (pinfunction "14_14") (pintype "bidirectional"))
    )
    (net (code "74") (name "SOLAR_CS3") (class "Default")
      (node (ref "X1") (pin "17") (pinfunction "17_17") (pintype "bidirectional"))
    )
    (net (code "75") (name "SOLAR_CS4") (class "Default")
      (node (ref "X1") (pin "16") (pinfunction "16_16") (pintype "bidirectional"))
    )
    (net (code "76") (name "SOLAR_CS5") (class "Default")
      (node (ref "X1") (pin "18") (pinfunction "18_18") (pintype "bidirectional"))
    )
    (net (code "77") (name "STRUT_GND") (class "Default")
      (node (ref "C1") (pin "1") (pinfunction "1_1") (pintype "passive"))
      (node (ref "H4") (pin "B3,2") (pinfunction "MOUNT_B3,2") (pintype "passive"))
      (node (ref "R1") (pin "P$2") (pinfunction "2_P$2") (pintype "passive"))
    )
    (net (code "78") (name "SUN") (class "Default")
      (node (ref "R12") (pin "2") (pinfunction "2_2") (pintype "passive"))
      (node (ref "X4") (pin "2") (pinfunction "2_2") (pintype "bidirectional"))
    )
    (net (code "79") (name "SUPERCAP_TEMP") (class "Default")
      (node (ref "X1") (pin "49") (pinfunction "49_49") (pintype "bidirectional"))
    )
    (net (code "80") (name "TEST") (class "Default")
      (node (ref "R14") (pin "2") (pinfunction "2_2") (pintype "passive"))
      (node (ref "U1") (pin "1") (pinfunction "1_1") (pintype "input"))
      (node (ref "X5") (pin "8") (pinfunction "8_8") (pintype "bidirectional"))
    )
    (net (code "81") (name "TXD") (class "Default")
      (node (ref "R7") (pin "1") (pinfunction "1_1") (pintype "passive"))
      (node (ref "X2") (pin "2") (pinfunction "2_2") (pintype "bidirectional"))
    )
    (net (code "82") (name "VBAT") (class "Default")
      (node (ref "X1") (pin "11") (pinfunction "11_11") (pintype "bidirectional"))
      (node (ref "X1") (pin "12") (pinfunction "12_12") (pintype "bidirectional"))
    )
    (net (code "83") (name "VBUS") (class "Default")
      (node (ref "U7") (pin "1") (pinfunction "P$1_1") (pintype "input"))
      (node (ref "U7") (pin "2") (pinfunction "P$2_2") (pintype "input"))
      (node (ref "X1") (pin "10") (pinfunction "10_10") (pintype "bidirectional"))
      (node (ref "X1") (pin "7") (pinfunction "7_7") (pintype "bidirectional"))
      (node (ref "X1") (pin "8") (pinfunction "8_8") (pintype "bidirectional"))
      (node (ref "X1") (pin "9") (pinfunction "9_9") (pintype "bidirectional"))
    )
    (net (code "84") (name "VSOLAR") (class "Default")
      (node (ref "X1") (pin "3") (pinfunction "3_3") (pintype "bidirectional"))
      (node (ref "X1") (pin "4") (pinfunction "4_4") (pintype "bidirectional"))
      (node (ref "X1") (pin "5") (pinfunction "5_5") (pintype "bidirectional"))
      (node (ref "X1") (pin "6") (pinfunction "6_6") (pintype "bidirectional"))
    )
    (net (code "85") (name "VSUPERCAP") (class "Default")
      (node (ref "R20") (pin "1") (pinfunction "1_1") (pintype "passive"))
      (node (ref "TP7") (pin "TP") (pinfunction "TP_TP") (pintype "input"))
      (node (ref "TR2") (pin "D") (pinfunction "D_D") (pintype "bidirectional"))
      (node (ref "X8") (pin "1") (pinfunction "1_1") (pintype "bidirectional"))
    )
    (net (code "86") (name "unconnected-(H1-MOUNT-PadB3,2)") (class "Default")
      (node (ref "H1") (pin "B3,2") (pinfunction "MOUNT_B3,2") (pintype "passive"))
    )
    (net (code "87") (name "unconnected-(H2-MOUNT-PadB3,2)") (class "Default")
      (node (ref "H2") (pin "B3,2") (pinfunction "MOUNT_B3,2") (pintype "passive"))
    )
    (net (code "88") (name "unconnected-(H3-MOUNT-PadB3,2)") (class "Default")
      (node (ref "H3") (pin "B3,2") (pinfunction "MOUNT_B3,2") (pintype "passive"))
    )
    (net (code "89") (name "unconnected-(U1-Pad11)") (class "Default")
      (node (ref "U1") (pin "11") (pinfunction "11_11") (pintype "bidirectional"))
    )
    (net (code "90") (name "unconnected-(U1-Pad17)") (class "Default")
      (node (ref "U1") (pin "17") (pinfunction "17_17") (pintype "bidirectional"))
    )
    (net (code "91") (name "unconnected-(U1-Pad19)") (class "Default")
      (node (ref "U1") (pin "19") (pinfunction "19_19") (pintype "bidirectional"))
    )
    (net (code "92") (name "unconnected-(U1-Pad20)") (class "Default")
      (node (ref "U1") (pin "20") (pinfunction "20_20") (pintype "bidirectional"))
    )
    (net (code "93") (name "unconnected-(U1-Pad21)") (class "Default")
      (node (ref "U1") (pin "21") (pinfunction "21_21") (pintype "bidirectional"))
    )
    (net (code "94") (name "unconnected-(U1-Pad22)") (class "Default")
      (node (ref "U1") (pin "22") (pinfunction "22_22") (pintype "bidirectional"))
    )
    (net (code "95") (name "unconnected-(U1-Pad23)") (class "Default")
      (node (ref "U1") (pin "23") (pinfunction "23_23") (pintype "bidirectional"))
    )
    (net (code "96") (name "unconnected-(U1-Pad24)") (class "Default")
      (node (ref "U1") (pin "24") (pinfunction "24_24") (pintype "bidirectional"))
    )
    (net (code "97") (name "unconnected-(U6-P$3-Pad3)") (class "Default")
      (node (ref "U6") (pin "3") (pinfunction "P$3_3") (pintype "input"))
    )
    (net (code "98") (name "unconnected-(X1-Pad13)") (class "Default")
      (node (ref "X1") (pin "13") (pinfunction "13_13") (pintype "bidirectional"))
    )
    (net (code "99") (name "unconnected-(X5-Pad2)") (class "Default")
      (node (ref "X5") (pin "2") (pinfunction "2_2") (pintype "bidirectional"))
    )
    (net (code "100") (name "unconnected-(X5-Pad6)") (class "Default")
      (node (ref "X5") (pin "6") (pinfunction "6_6") (pintype "bidirectional"))
    )
  )
)
